# Button3x4S-3_Sch.net
KiCad netlist of a schematic drawn in Altium Designer
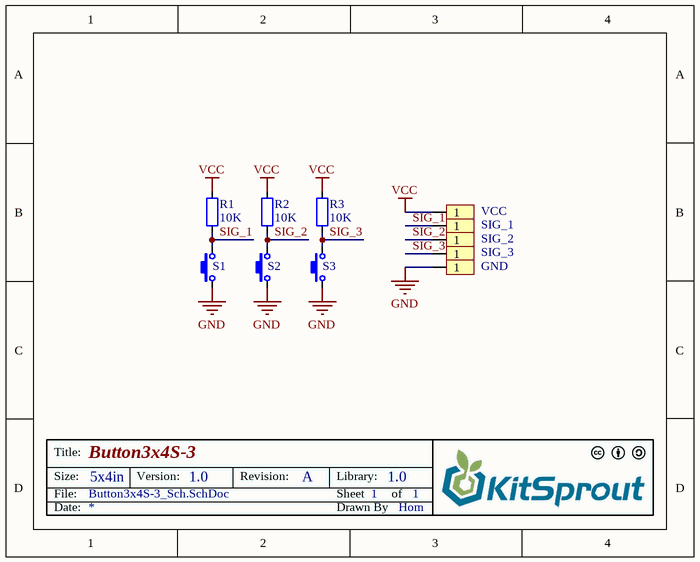
[diagram p0: Button3x4S-3_Sch.SchDoc]

(export (version "E")
  (design (tool "Eeschema 10.0.6"))
  (components
    (comp (ref "GND")
      (value "HDR-PAD_2.54")
      (footprint "PCB_ConnectorHDR:HDR-PAD_2.54")
      (description "Header")
      (libsource (lib "SCH_ConnectorHDR") (part "HDR-PAD_2.54"))
    )
    (comp (ref "R1")
      (value "10K")
      (footprint "PCB_PassiveRes:RES_0603")
      (description "Resistor")
      (fields (field (name "Comment") "Res_0603"))
      (libsource (lib "SCH_Passive") (part "Res_0603"))
    )
    (comp (ref "R2")
      (value "10K")
      (footprint "PCB_PassiveRes:RES_0603")
      (description "Resistor")
      (fields (field (name "Comment") "Res_0603"))
      (libsource (lib "SCH_Passive") (part "Res_0603"))
    )
    (comp (ref "R3")
      (value "10K")
      (footprint "PCB_PassiveRes:RES_0603")
      (description "Resistor")
      (fields (field (name "Comment") "Res_0603"))
      (libsource (lib "SCH_Passive") (part "Res_0603"))
    )
    (comp (ref "S1")
      (value "ButtonTACT_3x4x2_180")
      (footprint "PCB_Switch:ButtonTACT_3x4x2_180H")
      (description "Button")
      (libsource (lib "SCH_Switch") (part "ButtonTACT_3x4x2_180"))
    )
    (comp (ref "S2")
      (value "ButtonTACT_3x4x2_180")
      (footprint "PCB_Switch:ButtonTACT_3x4x2_180H")
      (description "Button")
      (libsource (lib "SCH_Switch") (part "ButtonTACT_3x4x2_180"))
    )
    (comp (ref "S3")
      (value "ButtonTACT_3x4x2_180")
      (footprint "PCB_Switch:ButtonTACT_3x4x2_180H")
      (description "Button")
      (libsource (lib "SCH_Switch") (part "ButtonTACT_3x4x2_180"))
    )
    (comp (ref "SIG_1")
      (value "HDR-PAD_2.54")
      (footprint "PCB_ConnectorHDR:HDR-PAD_2.54")
      (description "Header")
      (libsource (lib "SCH_ConnectorHDR") (part "HDR-PAD_2.54"))
    )
    (comp (ref "SIG_2")
      (value "HDR-PAD_2.54")
      (footprint "PCB_ConnectorHDR:HDR-PAD_2.54")
      (description "Header")
      (libsource (lib "SCH_ConnectorHDR") (part "HDR-PAD_2.54"))
    )
    (comp (ref "SIG_3")
      (value "HDR-PAD_2.54")
      (footprint "PCB_ConnectorHDR:HDR-PAD_2.54")
      (description "Header")
      (libsource (lib "SCH_ConnectorHDR") (part "HDR-PAD_2.54"))
    )
    (comp (ref "VCC")
      (value "HDR-PAD_2.54")
      (footprint "PCB_ConnectorHDR:HDR-PAD_2.54")
      (description "Header")
      (libsource (lib "SCH_ConnectorHDR") (part "HDR-PAD_2.54"))
    )
  )
  (nets
    (net (code "1") (name "/SIG_1") (class "Default")
      (node (ref "R1") (pin "1") (pinfunction "1_1") (pintype "passive"))
      (node (ref "S1") (pin "2") (pinfunction "2_2") (pintype "passive"))
      (node (ref "SIG_1") (pin "1") (pinfunction "1_1") (pintype "passive"))
    )
    (net (code "2") (name "/SIG_2") (class "Default")
      (node (ref "R2") (pin "1") (pinfunction "1_1") (pintype "passive"))
      (node (ref "S2") (pin "2") (pinfunction "2_2") (pintype "passive"))
      (node (ref "SIG_2") (pin "1") (pinfunction "1_1") (pintype "passive"))
    )
    (net (code "3") (name "/SIG_3") (class "Default")
      (node (ref "R3") (pin "1") (pinfunction "1_1") (pintype "passive"))
      (node (ref "S3") (pin "2") (pinfunction "2_2") (pintype "passive"))
      (node (ref "SIG_3") (pin "1") (pinfunction "1_1") (pintype "passive"))
    )
    (net (code "4") (name "GND") (class "Default")
      (node (ref "GND") (pin "1") (pinfunction "1_1") (pintype "passive"))
      (node (ref "S1") (pin "1") (pinfunction "1_1") (pintype "passive"))
      (node (ref "S2") (pin "1") (pinfunction "1_1") (pintype "passive"))
      (node (ref "S3") (pin "1") (pinfunction "1_1") (pintype "passive"))
    )
    (net (code "5") (name "VCC") (class "Default")
      (node (ref "R1") (pin "2") (pinfunction "2_2") (pintype "passive"))
      (node (ref "R2") (pin "2") (pinfunction "2_2") (pintype "passive"))
      (node (ref "R3") (pin "2") (pinfunction "2_2") (pintype "passive"))
      (node (ref "VCC") (pin "1") (pinfunction "1_1") (pintype "passive"))
    )
  )
)
